# NBT_I2C_INT.net
KiCad netlist of a schematic drawn in Altium Designer
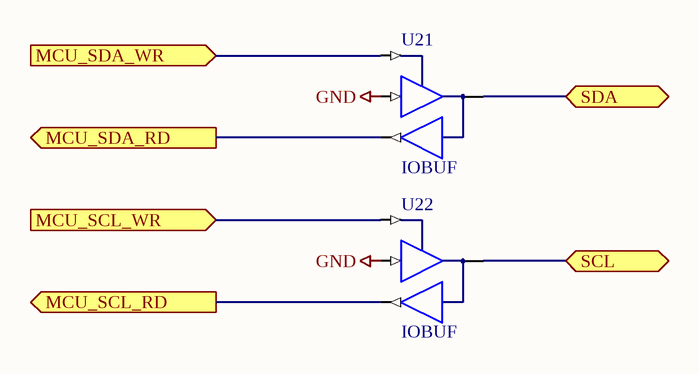
[diagram p0: NBT_I2C_INT.SCHDOC]

(export (version "E")
  (design (tool "Eeschema 10.0.6"))
  (components
    (comp (ref "U21")
      (value "IOBUF")
      (description "Input/Output Buffer")
      (fields (field (name "PUBLISHER") "Altium Limited"))
      (libsource (lib "FPGA Generic") (part "IOBUF"))
    )
    (comp (ref "U22")
      (value "IOBUF")
      (description "Input/Output Buffer")
      (fields (field (name "PUBLISHER") "Altium Limited"))
      (libsource (lib "FPGA Generic") (part "IOBUF"))
    )
  )
  (nets
    (net (code "1") (name "/MCU_SCL_RD") (class "Default")
      (node (ref "U22") (pin "O") (pinfunction "O_O") (pintype "output"))
    )
    (net (code "2") (name "/MCU_SCL_WR") (class "Default")
      (node (ref "U22") (pin "T") (pinfunction "T_T") (pintype "input"))
    )
    (net (code "3") (name "/MCU_SDA_RD") (class "Default")
      (node (ref "U21") (pin "O") (pinfunction "O_O") (pintype "output"))
    )
    (net (code "4") (name "/MCU_SDA_WR") (class "Default")
      (node (ref "U21") (pin "T") (pinfunction "T_T") (pintype "input"))
    )
    (net (code "5") (name "/SCL") (class "Default")
      (node (ref "U22") (pin "IO") (pinfunction "IO_IO") (pintype "bidirectional"))
    )
    (net (code "6") (name "/SDA") (class "Default")
      (node (ref "U21") (pin "IO") (pinfunction "IO_IO") (pintype "bidirectional"))
    )
    (net (code "7") (name "GND") (class "Default")
      (node (ref "U21") (pin "I") (pinfunction "I_I") (pintype "input"))
      (node (ref "U22") (pin "I") (pinfunction "I_I") (pintype "input"))
    )
  )
)
